# ADC_part1.net
KiCad netlist of a schematic drawn in Altium Designer
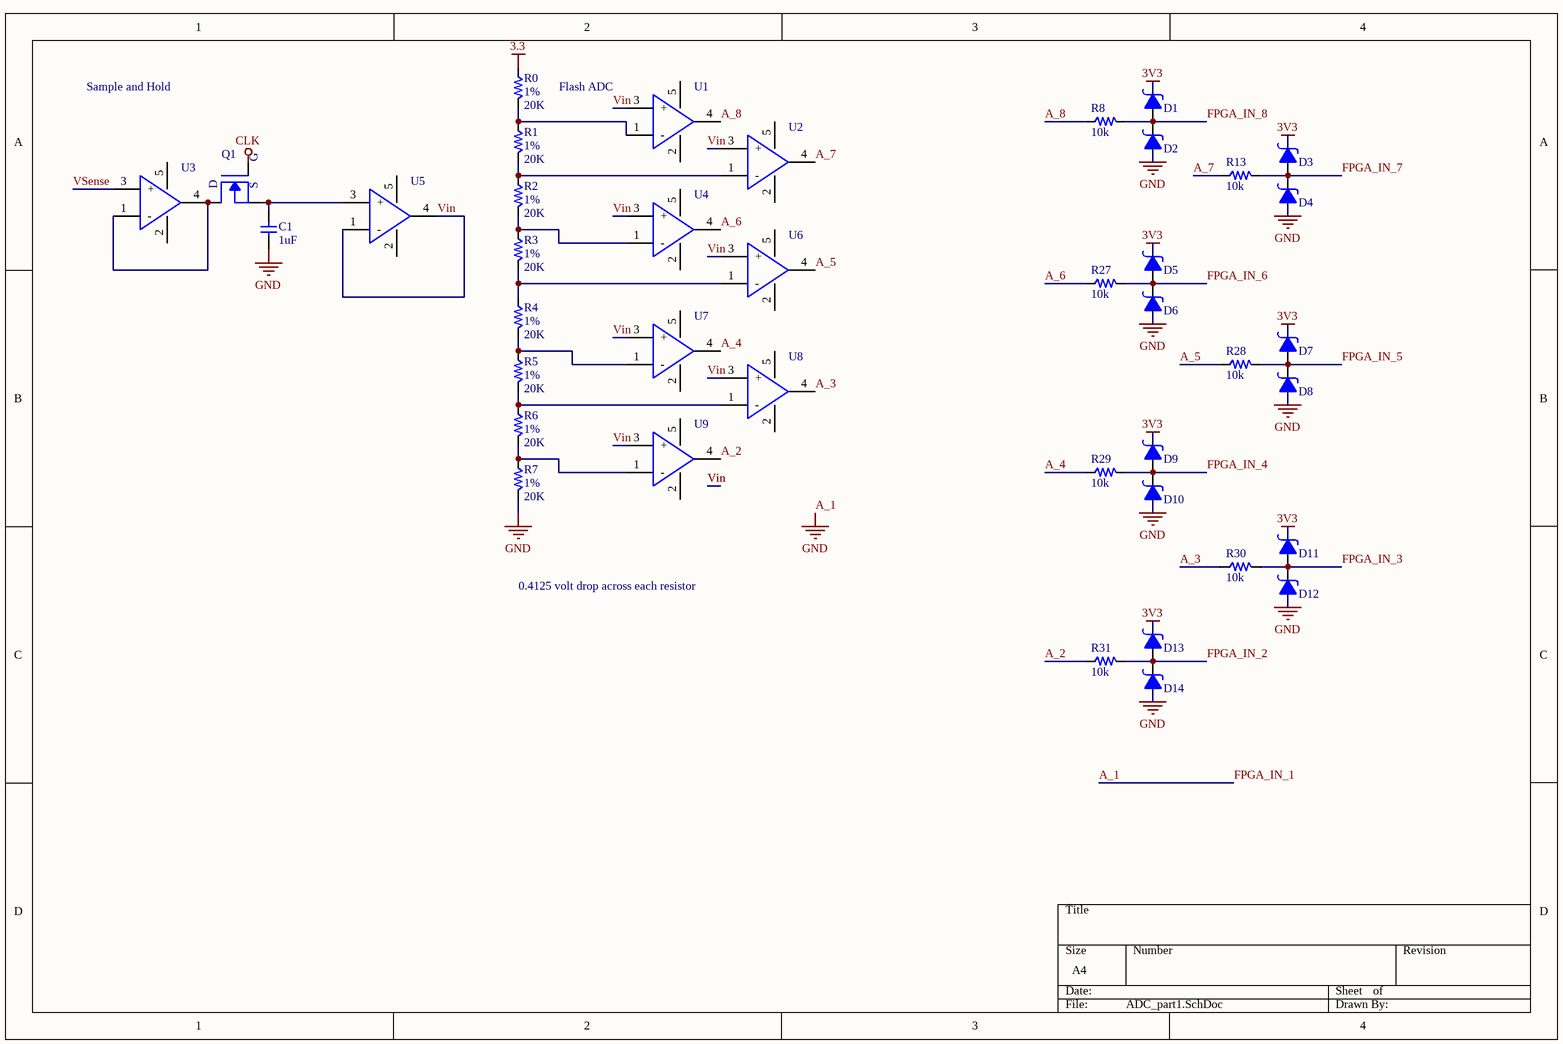
[diagram p0: ADC_part1.SchDoc]

(export (version "E")
  (design (tool "Eeschema 10.0.6"))
  (components
    (comp (ref "C1")
      (value "1uF")
      (footprint "PCB_GENERIC_SMD_0603")
      (description "CAP CER 0603 1uF 16V X5R 20%")
      (fields (field (name "TOLERANCE") "20%") (field (name "VOLTAGE") "16V"))
      (libsource (lib "CAP") (part "C060-0001U-00"))
    )
    (comp (ref "D1")
      (value "ONSEMI_MBRM110LT1G")
      (footprint "ON Semi Schottky Diode - MBRM110LT1G")
      (description "DIODE SCHOTTKY 10V 1A")
      (libsource (lib "ON Semi Schottky Diode") (part "ONSEMI_MBRM110LT1G"))
    )
    (comp (ref "D2")
      (value "ONSEMI_MBRM110LT1G")
      (footprint "ON Semi Schottky Diode - MBRM110LT1G")
      (description "DIODE SCHOTTKY 10V 1A")
      (libsource (lib "ON Semi Schottky Diode") (part "ONSEMI_MBRM110LT1G"))
    )
    (comp (ref "D3")
      (value "ONSEMI_MBRM110LT1G")
      (footprint "ON Semi Schottky Diode - MBRM110LT1G")
      (description "DIODE SCHOTTKY 10V 1A")
      (libsource (lib "ON Semi Schottky Diode") (part "ONSEMI_MBRM110LT1G"))
    )
    (comp (ref "D4")
      (value "ONSEMI_MBRM110LT1G")
      (footprint "ON Semi Schottky Diode - MBRM110LT1G")
      (description "DIODE SCHOTTKY 10V 1A")
      (libsource (lib "ON Semi Schottky Diode") (part "ONSEMI_MBRM110LT1G"))
    )
    (comp (ref "D5")
      (value "ONSEMI_MBRM110LT1G")
      (footprint "ON Semi Schottky Diode - MBRM110LT1G")
      (description "DIODE SCHOTTKY 10V 1A")
      (libsource (lib "ON Semi Schottky Diode") (part "ONSEMI_MBRM110LT1G"))
    )
    (comp (ref "D6")
      (value "ONSEMI_MBRM110LT1G")
      (footprint "ON Semi Schottky Diode - MBRM110LT1G")
      (description "DIODE SCHOTTKY 10V 1A")
      (libsource (lib "ON Semi Schottky Diode") (part "ONSEMI_MBRM110LT1G"))
    )
    (comp (ref "D7")
      (value "ONSEMI_MBRM110LT1G")
      (footprint "ON Semi Schottky Diode - MBRM110LT1G")
      (description "DIODE SCHOTTKY 10V 1A")
      (libsource (lib "ON Semi Schottky Diode") (part "ONSEMI_MBRM110LT1G"))
    )
    (comp (ref "D8")
      (value "ONSEMI_MBRM110LT1G")
      (footprint "ON Semi Schottky Diode - MBRM110LT1G")
      (description "DIODE SCHOTTKY 10V 1A")
      (libsource (lib "ON Semi Schottky Diode") (part "ONSEMI_MBRM110LT1G"))
    )
    (comp (ref "D9")
      (value "ONSEMI_MBRM110LT1G")
      (footprint "ON Semi Schottky Diode - MBRM110LT1G")
      (description "DIODE SCHOTTKY 10V 1A")
      (libsource (lib "ON Semi Schottky Diode") (part "ONSEMI_MBRM110LT1G"))
    )
    (comp (ref "D10")
      (value "ONSEMI_MBRM110LT1G")
      (footprint "ON Semi Schottky Diode - MBRM110LT1G")
      (description "DIODE SCHOTTKY 10V 1A")
      (libsource (lib "ON Semi Schottky Diode") (part "ONSEMI_MBRM110LT1G"))
    )
    (comp (ref "D11")
      (value "ONSEMI_MBRM110LT1G")
      (footprint "ON Semi Schottky Diode - MBRM110LT1G")
      (description "DIODE SCHOTTKY 10V 1A")
      (libsource (lib "ON Semi Schottky Diode") (part "ONSEMI_MBRM110LT1G"))
    )
    (comp (ref "D12")
      (value "ONSEMI_MBRM110LT1G")
      (footprint "ON Semi Schottky Diode - MBRM110LT1G")
      (description "DIODE SCHOTTKY 10V 1A")
      (libsource (lib "ON Semi Schottky Diode") (part "ONSEMI_MBRM110LT1G"))
    )
    (comp (ref "D13")
      (value "ONSEMI_MBRM110LT1G")
      (footprint "ON Semi Schottky Diode - MBRM110LT1G")
      (description "DIODE SCHOTTKY 10V 1A")
      (libsource (lib "ON Semi Schottky Diode") (part "ONSEMI_MBRM110LT1G"))
    )
    (comp (ref "D14")
      (value "ONSEMI_MBRM110LT1G")
      (footprint "ON Semi Schottky Diode - MBRM110LT1G")
      (description "DIODE SCHOTTKY 10V 1A")
      (libsource (lib "ON Semi Schottky Diode") (part "ONSEMI_MBRM110LT1G"))
    )
    (comp (ref "Q1")
      (value "NMOS - SSM3K333R")
      (footprint "NMOS - SSM3K333R - SOTFL95P180X88-3M")
      (description "MOSFET N CH 30V 6A 2-3Z1A")
      (libsource (lib "NMOS") (part "NMOS - SSM3K333R"))
    )
    (comp (ref "R0")
      (value "20K")
      (footprint "PCB_GENERIC_SMD_0603")
      (description "RES 0603 10K 1% 100mW")
      (fields
        (field (name "POWER") "100mW")
        (field (name "TOLERANCE") "1%")
        (field (name "Comment") "R060-00103-01")
      )
      (libsource (lib "RES") (part "R060-00103-01"))
    )
    (comp (ref "R1")
      (value "20K")
      (footprint "PCB_GENERIC_SMD_0603")
      (description "RES 0603 10K 1% 100mW")
      (fields
        (field (name "POWER") "100mW")
        (field (name "TOLERANCE") "1%")
        (field (name "Comment") "R060-00103-01")
      )
      (libsource (lib "RES") (part "R060-00103-01"))
    )
    (comp (ref "R2")
      (value "20K")
      (footprint "PCB_GENERIC_SMD_0603")
      (description "RES 0603 10K 1% 100mW")
      (fields
        (field (name "POWER") "100mW")
        (field (name "TOLERANCE") "1%")
        (field (name "Comment") "R060-00103-01")
      )
      (libsource (lib "RES") (part "R060-00103-01"))
    )
    (comp (ref "R3")
      (value "20K")
      (footprint "PCB_GENERIC_SMD_0603")
      (description "RES 0603 10K 1% 100mW")
      (fields
        (field (name "POWER") "100mW")
        (field (name "TOLERANCE") "1%")
        (field (name "Comment") "R060-00103-01")
      )
      (libsource (lib "RES") (part "R060-00103-01"))
    )
    (comp (ref "R4")
      (value "20K")
      (footprint "PCB_GENERIC_SMD_0603")
      (description "RES 0603 10K 1% 100mW")
      (fields
        (field (name "POWER") "100mW")
        (field (name "TOLERANCE") "1%")
        (field (name "Comment") "R060-00103-01")
      )
      (libsource (lib "RES") (part "R060-00103-01"))
    )
    (comp (ref "R5")
      (value "20K")
      (footprint "PCB_GENERIC_SMD_0603")
      (description "RES 0603 10K 1% 100mW")
      (fields
        (field (name "POWER") "100mW")
        (field (name "TOLERANCE") "1%")
        (field (name "Comment") "R060-00103-01")
      )
      (libsource (lib "RES") (part "R060-00103-01"))
    )
    (comp (ref "R6")
      (value "20K")
      (footprint "PCB_GENERIC_SMD_0603")
      (description "RES 0603 10K 1% 100mW")
      (fields
        (field (name "POWER") "100mW")
        (field (name "TOLERANCE") "1%")
        (field (name "Comment") "R060-00103-01")
      )
      (libsource (lib "RES") (part "R060-00103-01"))
    )
    (comp (ref "R7")
      (value "20K")
      (footprint "PCB_GENERIC_SMD_0603")
      (description "RES 0603 10K 1% 100mW")
      (fields
        (field (name "POWER") "100mW")
        (field (name "TOLERANCE") "1%")
        (field (name "Comment") "R060-00103-01")
      )
      (libsource (lib "RES") (part "R060-00103-01"))
    )
    (comp (ref "R8")
      (value "10k")
      (footprint "PCB_GENERIC_SMD_0603")
      (description "RES 0603 100ohm 5% 63mW")
      (fields (field (name "TOLERANCE") "5%") (field (name "POWER") "63mW"))
      (libsource (lib "RES") (part "R060-00101-05"))
    )
    (comp (ref "R13")
      (value "10k")
      (footprint "PCB_GENERIC_SMD_0603")
      (description "RES 0603 100ohm 5% 63mW")
      (fields (field (name "TOLERANCE") "5%") (field (name "POWER") "63mW"))
      (libsource (lib "RES") (part "R060-00101-05"))
    )
    (comp (ref "R27")
      (value "10k")
      (footprint "PCB_GENERIC_SMD_0603")
      (description "RES 0603 100ohm 5% 63mW")
      (fields (field (name "TOLERANCE") "5%") (field (name "POWER") "63mW"))
      (libsource (lib "RES") (part "R060-00101-05"))
    )
    (comp (ref "R28")
      (value "10k")
      (footprint "PCB_GENERIC_SMD_0603")
      (description "RES 0603 100ohm 5% 63mW")
      (fields (field (name "TOLERANCE") "5%") (field (name "POWER") "63mW"))
      (libsource (lib "RES") (part "R060-00101-05"))
    )
    (comp (ref "R29")
      (value "10k")
      (footprint "PCB_GENERIC_SMD_0603")
      (description "RES 0603 100ohm 5% 63mW")
      (fields (field (name "TOLERANCE") "5%") (field (name "POWER") "63mW"))
      (libsource (lib "RES") (part "R060-00101-05"))
    )
    (comp (ref "R30")
      (value "10k")
      (footprint "PCB_GENERIC_SMD_0603")
      (description "RES 0603 100ohm 5% 63mW")
      (fields (field (name "TOLERANCE") "5%") (field (name "POWER") "63mW"))
      (libsource (lib "RES") (part "R060-00101-05"))
    )
    (comp (ref "R31")
      (value "10k")
      (footprint "PCB_GENERIC_SMD_0603")
      (description "RES 0603 100ohm 5% 63mW")
      (fields (field (name "TOLERANCE") "5%") (field (name "POWER") "63mW"))
      (libsource (lib "RES") (part "R060-00101-05"))
    )
    (comp (ref "U1")
      (value "AP331A")
      (footprint "SOT95P285X130-5N")
      (description "Single Channel Comparator, Open Drain, SC-74A/SOT-753")
      (libsource (lib "Op_Amp") (part "AP331A"))
    )
    (comp (ref "U2")
      (value "AP331A")
      (footprint "SOT95P285X130-5N")
      (description "Single Channel Comparator, Open Drain, SC-74A/SOT-753")
      (libsource (lib "Op_Amp") (part "AP331A"))
    )
    (comp (ref "U3")
      (value "AP331A")
      (footprint "SOT95P285X130-5N")
      (description "Single Channel Comparator, Open Drain, SC-74A/SOT-753")
      (libsource (lib "Op_Amp") (part "AP331A"))
    )
    (comp (ref "U4")
      (value "AP331A")
      (footprint "SOT95P285X130-5N")
      (description "Single Channel Comparator, Open Drain, SC-74A/SOT-753")
      (libsource (lib "Op_Amp") (part "AP331A"))
    )
    (comp (ref "U5")
      (value "AP331A")
      (footprint "SOT95P285X130-5N")
      (description "Single Channel Comparator, Open Drain, SC-74A/SOT-753")
      (libsource (lib "Op_Amp") (part "AP331A"))
    )
    (comp (ref "U6")
      (value "AP331A")
      (footprint "SOT95P285X130-5N")
      (description "Single Channel Comparator, Open Drain, SC-74A/SOT-753")
      (libsource (lib "Op_Amp") (part "AP331A"))
    )
    (comp (ref "U7")
      (value "AP331A")
      (footprint "SOT95P285X130-5N")
      (description "Single Channel Comparator, Open Drain, SC-74A/SOT-753")
      (libsource (lib "Op_Amp") (part "AP331A"))
    )
    (comp (ref "U8")
      (value "AP331A")
      (footprint "SOT95P285X130-5N")
      (description "Single Channel Comparator, Open Drain, SC-74A/SOT-753")
      (libsource (lib "Op_Amp") (part "AP331A"))
    )
    (comp (ref "U9")
      (value "AP331A")
      (footprint "SOT95P285X130-5N")
      (description "Single Channel Comparator, Open Drain, SC-74A/SOT-753")
      (libsource (lib "Op_Amp") (part "AP331A"))
    )
  )
  (nets
    (net (code "1") (name "/A_2") (class "Default")
      (node (ref "R31") (pin "1") (pinfunction "1_1") (pintype "passive"))
      (node (ref "U9") (pin "4") (pinfunction "VOUT_4") (pintype "passive"))
    )
    (net (code "2") (name "/A_3") (class "Default")
      (node (ref "R30") (pin "1") (pinfunction "1_1") (pintype "passive"))
      (node (ref "U8") (pin "4") (pinfunction "VOUT_4") (pintype "passive"))
    )
    (net (code "3") (name "/A_4") (class "Default")
      (node (ref "R29") (pin "1") (pinfunction "1_1") (pintype "passive"))
      (node (ref "U7") (pin "4") (pinfunction "VOUT_4") (pintype "passive"))
    )
    (net (code "4") (name "/A_5") (class "Default")
      (node (ref "R28") (pin "1") (pinfunction "1_1") (pintype "passive"))
      (node (ref "U6") (pin "4") (pinfunction "VOUT_4") (pintype "passive"))
    )
    (net (code "5") (name "/A_6") (class "Default")
      (node (ref "R27") (pin "1") (pinfunction "1_1") (pintype "passive"))
      (node (ref "U4") (pin "4") (pinfunction "VOUT_4") (pintype "passive"))
    )
    (net (code "6") (name "/A_7") (class "Default")
      (node (ref "R13") (pin "1") (pinfunction "1_1") (pintype "passive"))
      (node (ref "U2") (pin "4") (pinfunction "VOUT_4") (pintype "passive"))
    )
    (net (code "7") (name "/A_8") (class "Default")
      (node (ref "R8") (pin "1") (pinfunction "1_1") (pintype "passive"))
      (node (ref "U1") (pin "4") (pinfunction "VOUT_4") (pintype "passive"))
    )
    (net (code "8") (name "/FPGA_IN_2") (class "Default")
      (node (ref "D13") (pin "2") (pinfunction "2_2") (pintype "passive"))
      (node (ref "D14") (pin "1") (pinfunction "1_1") (pintype "passive"))
      (node (ref "R31") (pin "2") (pinfunction "2_2") (pintype "passive"))
    )
    (net (code "9") (name "/FPGA_IN_3") (class "Default")
      (node (ref "D11") (pin "2") (pinfunction "2_2") (pintype "passive"))
      (node (ref "D12") (pin "1") (pinfunction "1_1") (pintype "passive"))
      (node (ref "R30") (pin "2") (pinfunction "2_2") (pintype "passive"))
    )
    (net (code "10") (name "/FPGA_IN_4") (class "Default")
      (node (ref "D10") (pin "1") (pinfunction "1_1") (pintype "passive"))
      (node (ref "D9") (pin "2") (pinfunction "2_2") (pintype "passive"))
      (node (ref "R29") (pin "2") (pinfunction "2_2") (pintype "passive"))
    )
    (net (code "11") (name "/FPGA_IN_5") (class "Default")
      (node (ref "D7") (pin "2") (pinfunction "2_2") (pintype "passive"))
      (node (ref "D8") (pin "1") (pinfunction "1_1") (pintype "passive"))
      (node (ref "R28") (pin "2") (pinfunction "2_2") (pintype "passive"))
    )
    (net (code "12") (name "/FPGA_IN_6") (class "Default")
      (node (ref "D5") (pin "2") (pinfunction "2_2") (pintype "passive"))
      (node (ref "D6") (pin "1") (pinfunction "1_1") (pintype "passive"))
      (node (ref "R27") (pin "2") (pinfunction "2_2") (pintype "passive"))
    )
    (net (code "13") (name "/FPGA_IN_7") (class "Default")
      (node (ref "D3") (pin "2") (pinfunction "2_2") (pintype "passive"))
      (node (ref "D4") (pin "1") (pinfunction "1_1") (pintype "passive"))
      (node (ref "R13") (pin "2") (pinfunction "2_2") (pintype "passive"))
    )
    (net (code "14") (name "/FPGA_IN_8") (class "Default")
      (node (ref "D1") (pin "2") (pinfunction "2_2") (pintype "passive"))
      (node (ref "D2") (pin "1") (pinfunction "1_1") (pintype "passive"))
      (node (ref "R8") (pin "2") (pinfunction "2_2") (pintype "passive"))
    )
    (net (code "15") (name "/VSense") (class "Default")
      (node (ref "U3") (pin "3") (pinfunction "+_3") (pintype "passive"))
    )
    (net (code "16") (name "/Vin") (class "Default")
      (node (ref "U1") (pin "3") (pinfunction "+_3") (pintype "passive"))
      (node (ref "U2") (pin "3") (pinfunction "+_3") (pintype "passive"))
      (node (ref "U4") (pin "3") (pinfunction "+_3") (pintype "passive"))
      (node (ref "U5") (pin "1") (pinfunction "-_1") (pintype "passive"))
      (node (ref "U5") (pin "4") (pinfunction "VOUT_4") (pintype "passive"))
      (node (ref "U6") (pin "3") (pinfunction "+_3") (pintype "passive"))
      (node (ref "U7") (pin "3") (pinfunction "+_3") (pintype "passive"))
      (node (ref "U8") (pin "3") (pinfunction "+_3") (pintype "passive"))
      (node (ref "U9") (pin "3") (pinfunction "+_3") (pintype "passive"))
    )
    (net (code "17") (name "3.3") (class "Default")
      (node (ref "R0") (pin "1") (pinfunction "1_1") (pintype "passive"))
    )
    (net (code "18") (name "3V3") (class "Default")
      (node (ref "D1") (pin "1") (pinfunction "1_1") (pintype "passive"))
      (node (ref "D11") (pin "1") (pinfunction "1_1") (pintype "passive"))
      (node (ref "D13") (pin "1") (pinfunction "1_1") (pintype "passive"))
      (node (ref "D3") (pin "1") (pinfunction "1_1") (pintype "passive"))
      (node (ref "D5") (pin "1") (pinfunction "1_1") (pintype "passive"))
      (node (ref "D7") (pin "1") (pinfunction "1_1") (pintype "passive"))
      (node (ref "D9") (pin "1") (pinfunction "1_1") (pintype "passive"))
    )
    (net (code "19") (name "CLK") (class "Default")
      (node (ref "Q1") (pin "1") (pinfunction "G_1") (pintype "passive"))
    )
    (net (code "20") (name "GND") (class "Default")
      (node (ref "C1") (pin "1") (pinfunction "1_1") (pintype "passive"))
      (node (ref "D10") (pin "2") (pinfunction "2_2") (pintype "passive"))
      (node (ref "D12") (pin "2") (pinfunction "2_2") (pintype "passive"))
      (node (ref "D14") (pin "2") (pinfunction "2_2") (pintype "passive"))
      (node (ref "D2") (pin "2") (pinfunction "2_2") (pintype "passive"))
      (node (ref "D4") (pin "2") (pinfunction "2_2") (pintype "passive"))
      (node (ref "D6") (pin "2") (pinfunction "2_2") (pintype "passive"))
      (node (ref "D8") (pin "2") (pinfunction "2_2") (pintype "passive"))
      (node (ref "R7") (pin "2") (pinfunction "2_2") (pintype "passive"))
    )
    (net (code "21") (name "Net-(Q1-D)") (class "Default")
      (node (ref "Q1") (pin "3") (pinfunction "D_3") (pintype "passive"))
      (node (ref "U3") (pin "1") (pinfunction "-_1") (pintype "passive"))
      (node (ref "U3") (pin "4") (pinfunction "VOUT_4") (pintype "passive"))
    )
    (net (code "22") (name "Net-(Q1-S)") (class "Default")
      (node (ref "C1") (pin "2") (pinfunction "2_2") (pintype "passive"))
      (node (ref "Q1") (pin "2") (pinfunction "S_2") (pintype "passive"))
      (node (ref "U5") (pin "3") (pinfunction "+_3") (pintype "passive"))
    )
    (net (code "23") (name "Net-(U1--)") (class "Default")
      (node (ref "R0") (pin "2") (pinfunction "2_2") (pintype "passive"))
      (node (ref "R1") (pin "1") (pinfunction "1_1") (pintype "passive"))
      (node (ref "U1") (pin "1") (pinfunction "-_1") (pintype "passive"))
    )
    (net (code "24") (name "Net-(U2--)") (class "Default")
      (node (ref "R1") (pin "2") (pinfunction "2_2") (pintype "passive"))
      (node (ref "R2") (pin "1") (pinfunction "1_1") (pintype "passive"))
      (node (ref "U2") (pin "1") (pinfunction "-_1") (pintype "passive"))
    )
    (net (code "25") (name "Net-(U4--)") (class "Default")
      (node (ref "R2") (pin "2") (pinfunction "2_2") (pintype "passive"))
      (node (ref "R3") (pin "1") (pinfunction "1_1") (pintype "passive"))
      (node (ref "U4") (pin "1") (pinfunction "-_1") (pintype "passive"))
    )
    (net (code "26") (name "Net-(U6--)") (class "Default")
      (node (ref "R3") (pin "2") (pinfunction "2_2") (pintype "passive"))
      (node (ref "R4") (pin "1") (pinfunction "1_1") (pintype "passive"))
      (node (ref "U6") (pin "1") (pinfunction "-_1") (pintype "passive"))
    )
    (net (code "27") (name "Net-(U7--)") (class "Default")
      (node (ref "R4") (pin "2") (pinfunction "2_2") (pintype "passive"))
      (node (ref "R5") (pin "1") (pinfunction "1_1") (pintype "passive"))
      (node (ref "U7") (pin "1") (pinfunction "-_1") (pintype "passive"))
    )
    (net (code "28") (name "Net-(U8--)") (class "Default")
      (node (ref "R5") (pin "2") (pinfunction "2_2") (pintype "passive"))
      (node (ref "R6") (pin "1") (pinfunction "1_1") (pintype "passive"))
      (node (ref "U8") (pin "1") (pinfunction "-_1") (pintype "passive"))
    )
    (net (code "29") (name "Net-(U9--)") (class "Default")
      (node (ref "R6") (pin "2") (pinfunction "2_2") (pintype "passive"))
      (node (ref "R7") (pin "1") (pinfunction "1_1") (pintype "passive"))
      (node (ref "U9") (pin "1") (pinfunction "-_1") (pintype "passive"))
    )
    (net (code "30") (name "unconnected-(U1-GND-Pad2)") (class "Default")
      (node (ref "U1") (pin "2") (pinfunction "GND_2") (pintype "passive"))
    )
    (net (code "31") (name "unconnected-(U1-VCC-Pad5)") (class "Default")
      (node (ref "U1") (pin "5") (pinfunction "VCC_5") (pintype "passive"))
    )
    (net (code "32") (name "unconnected-(U2-GND-Pad2)") (class "Default")
      (node (ref "U2") (pin "2") (pinfunction "GND_2") (pintype "passive"))
    )
    (net (code "33") (name "unconnected-(U2-VCC-Pad5)") (class "Default")
      (node (ref "U2") (pin "5") (pinfunction "VCC_5") (pintype "passive"))
    )
    (net (code "34") (name "unconnected-(U3-GND-Pad2)") (class "Default")
      (node (ref "U3") (pin "2") (pinfunction "GND_2") (pintype "passive"))
    )
    (net (code "35") (name "unconnected-(U3-VCC-Pad5)") (class "Default")
      (node (ref "U3") (pin "5") (pinfunction "VCC_5") (pintype "passive"))
    )
    (net (code "36") (name "unconnected-(U4-GND-Pad2)") (class "Default")
      (node (ref "U4") (pin "2") (pinfunction "GND_2") (pintype "passive"))
    )
    (net (code "37") (name "unconnected-(U4-VCC-Pad5)") (class "Default")
      (node (ref "U4") (pin "5") (pinfunction "VCC_5") (pintype "passive"))
    )
    (net (code "38") (name "unconnected-(U5-GND-Pad2)") (class "Default")
      (node (ref "U5") (pin "2") (pinfunction "GND_2") (pintype "passive"))
    )
    (net (code "39") (name "unconnected-(U5-VCC-Pad5)") (class "Default")
      (node (ref "U5") (pin "5") (pinfunction "VCC_5") (pintype "passive"))
    )
    (net (code "40") (name "unconnected-(U6-GND-Pad2)") (class "Default")
      (node (ref "U6") (pin "2") (pinfunction "GND_2") (pintype "passive"))
    )
    (net (code "41") (name "unconnected-(U6-VCC-Pad5)") (class "Default")
      (node (ref "U6") (pin "5") (pinfunction "VCC_5") (pintype "passive"))
    )
    (net (code "42") (name "unconnected-(U7-GND-Pad2)") (class "Default")
      (node (ref "U7") (pin "2") (pinfunction "GND_2") (pintype "passive"))
    )
    (net (code "43") (name "unconnected-(U7-VCC-Pad5)") (class "Default")
      (node (ref "U7") (pin "5") (pinfunction "VCC_5") (pintype "passive"))
    )
    (net (code "44") (name "unconnected-(U8-GND-Pad2)") (class "Default")
      (node (ref "U8") (pin "2") (pinfunction "GND_2") (pintype "passive"))
    )
    (net (code "45") (name "unconnected-(U8-VCC-Pad5)") (class "Default")
      (node (ref "U8") (pin "5") (pinfunction "VCC_5") (pintype "passive"))
    )
    (net (code "46") (name "unconnected-(U9-GND-Pad2)") (class "Default")
      (node (ref "U9") (pin "2") (pinfunction "GND_2") (pintype "passive"))
    )
    (net (code "47") (name "unconnected-(U9-VCC-Pad5)") (class "Default")
      (node (ref "U9") (pin "5") (pinfunction "VCC_5") (pintype "passive"))
    )
  )
)
